# Power_Board.net
KiCad netlist of a schematic drawn in Altium Designer
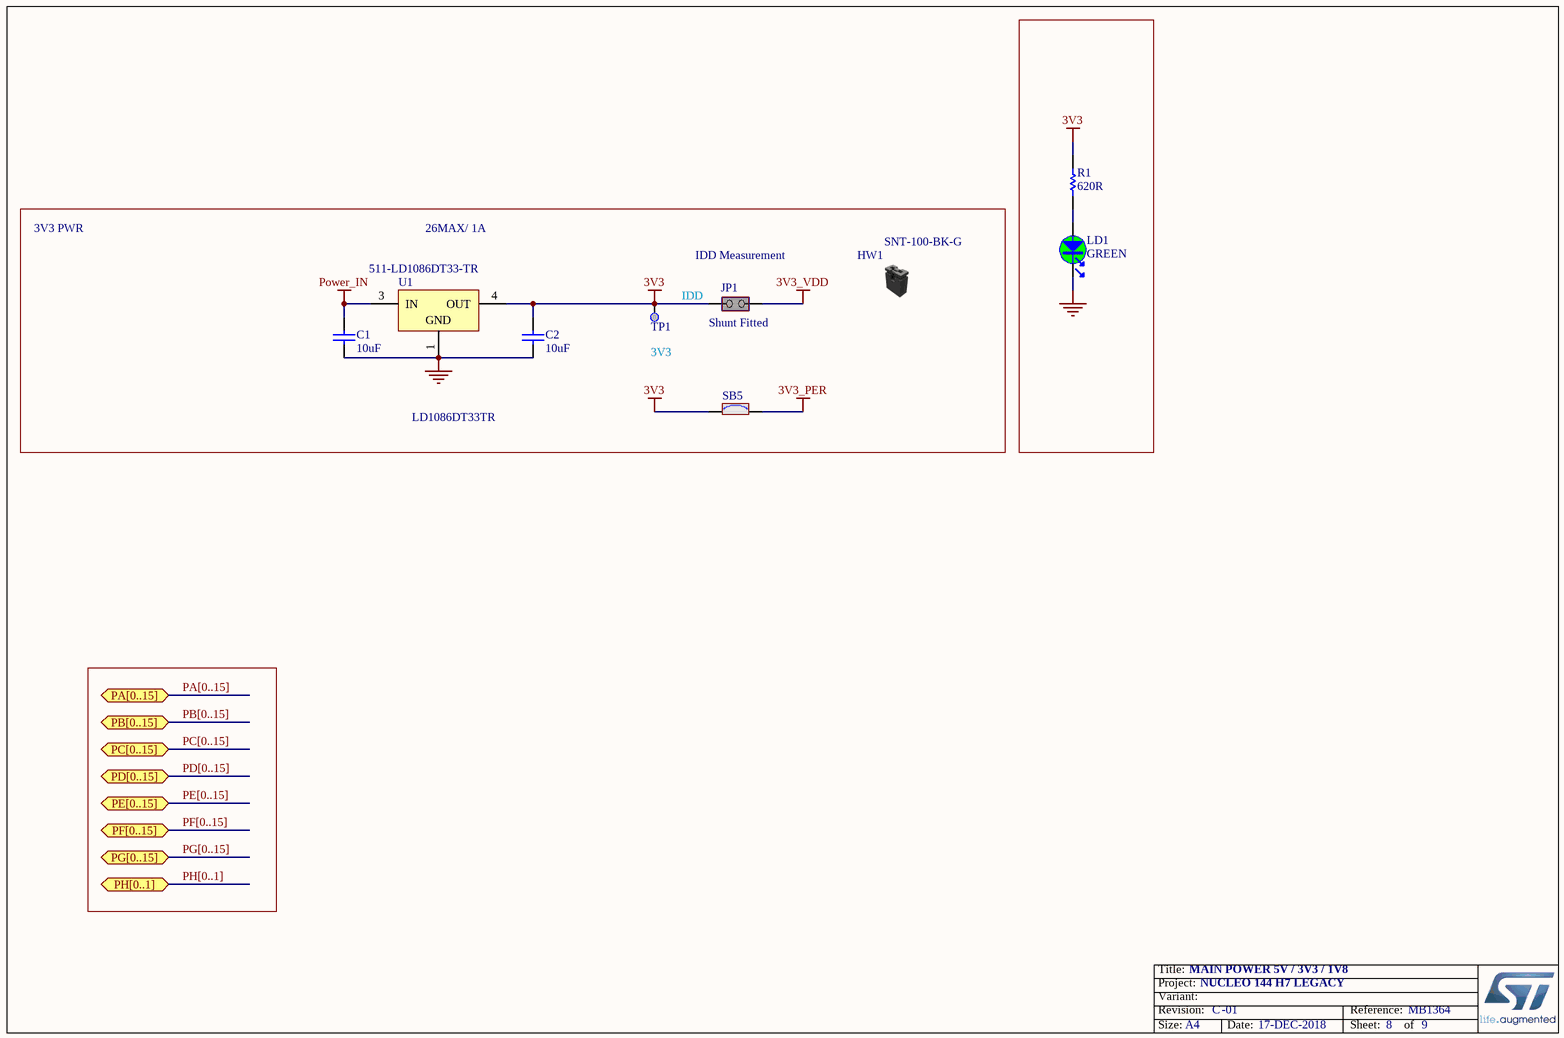
[diagram p0: Power_Board.SchDoc]

(export (version "E")
  (design (tool "Eeschema 10.0.6"))
  (components
    (comp (ref "C1")
      (value "10uF")
      (footprint "C0805")
      (description "Capacitor, MLCC, 10uF, 25V, X5R, 10%, 0805, T=0,85mm")
      (fields
        (field (name "INTERNAL_PART_NUMBER") "MCD-00014")
        (field (name "MANUFACTURER_PART_NUMBER") "CC0805KRX5R8BB106")
        (field (name "PROVIDED_BY") "SUBCO")
      )
      (libsource (lib "MCD_PARTS_database") (part "Capacitor"))
    )
    (comp (ref "C2")
      (value "10uF")
      (footprint "C0805")
      (description "Capacitor, MLCC, 10uF, 25V, X5R, 10%, 0805, T=0,85mm")
      (fields
        (field (name "INTERNAL_PART_NUMBER") "MCD-00014")
        (field (name "MANUFACTURER_PART_NUMBER") "CC0805KRX5R8BB106")
        (field (name "PROVIDED_BY") "SUBCO")
      )
      (libsource (lib "MCD_PARTS_database") (part "Capacitor"))
    )
    (comp (ref "HW1")
      (value "SNT-100-BK-G")
      (description "SHUNT 2.54mm BLACK")
      (fields
        (field (name "INTERNAL_PART_NUMBER") "MCD-00043")
        (field (name "MANUFACTURER") "SAMTEC")
        (field (name "PROVIDED_BY") "SUBCO")
      )
      (libsource (lib "MCD_PARTS_database") (part "Shunt Black 2.54mm"))
    )
    (comp (ref "JP1")
      (value "Shunt Fitted")
      (footprint "CON_SAMTEC_TSW-102-07-G-S")
      (description "Header, 2x1, 2,54mm, VR, TH, Height 5.84mm/2.54mm - Shunt Fitted by default")
      (fields
        (field (name "INTERNAL_PART_NUMBER") "MCD-00683")
        (field (name "MANUFACTURER_PART_NUMBER") "TSW-102-07-x-S")
        (field (name "PROVIDED_BY") "SUBCO")
      )
      (libsource (lib "MCD_PARTS_database") (part "Jumper_Header 2x1 Fitted"))
    )
    (comp (ref "LD1")
      (value "GREEN")
      (footprint "LED_0603_OSRAM_LG-Q396-PS-35_GREEN_1A2K_H0P4")
      (description "LED Green, 0603 SMD, Forward Voltage Typ=2V, Max=2.5V")
      (fields
        (field (name "INTERNAL_PART_NUMBER") "MCD-00588")
        (field (name "MANUFACTURER_PART_NUMBER") "LG Q396-PS-35")
        (field (name "PROVIDED_BY") "SUBCO")
      )
      (libsource (lib "MCD_PARTS_database") (part "LED_green"))
    )
    (comp (ref "R1")
      (value "620R")
      (footprint "R0603")
      (description "Resistor,620R,0603,1%,1/10W")
      (fields
        (field (name "INTERNAL_PART_NUMBER") "MCD-00500")
        (field (name "MANUFACTURER_PART_NUMBER") "RC0603FR-07620RL")
        (field (name "PROVIDED_BY") "SUBCO")
      )
      (libsource (lib "MCD_PARTS_database") (part "Resistor"))
    )
    (comp (ref "SB5")
      (value "SB_ON")
      (footprint "SOLDER-BRIDGE_R0603-0R")
      (description "Solder Bridge ON")
      (fields
        (field (name "INTERNAL_PART_NUMBER") "MCD-00071")
        (field (name "MANUFACTURER_PART_NUMBER") "RC0603JR-070RL")
        (field (name "PROVIDED_BY") "SUBCO")
      )
      (libsource (lib "MCD_PARTS_database") (part "SB_ON"))
    )
    (comp (ref "TP1")
      (value "Test Point")
      (footprint "TP_SMD_1MM")
      (description "Test Point 1mm")
      (fields (field (name "INTERNAL_PART_NUMBER") "MCD-00074") (field (name "MANUFACTURER") "n/a"))
      (libsource (lib "MCD_PARTS_database") (part "Test Point"))
    )
    (comp (ref "U1")
      (value "LD1086DT33TR")
      (footprint "TO-252_L")
      (description "1.5A, Low Drop Positive Voltage Regulator, 3.3V, 3-Pin DPAK, Tape and Reel")
      (fields
        (field (name "SUPPLIER PART NUMBER 1") "511-LD1086DT33-TR")
        (field (name "MANUFACTURER") "STMicroelectronics")
      )
      (libsource (lib "Altium Content Vault") (part "PM-REG-LD1085-SOT3"))
    )
  )
  (nets
    (net (code "123") (name "3V3") (class "Default")
      (node (ref "C2") (pin "2") (pinfunction "2_2") (pintype "passive"))
      (node (ref "JP1") (pin "1") (pinfunction "COMMON_1") (pintype "passive"))
      (node (ref "R1") (pin "2") (pinfunction "2_2") (pintype "passive"))
      (node (ref "SB5") (pin "1") (pinfunction "1_1") (pintype "passive"))
      (node (ref "TP1") (pin "1") (pinfunction "1_1") (pintype "passive"))
      (node (ref "U1") (pin "4") (pinfunction "OUT_4") (pintype "power_in"))
    )
    (net (code "124") (name "3V3_PER") (class "Default")
      (node (ref "SB5") (pin "2") (pinfunction "2_2") (pintype "passive"))
    )
    (net (code "125") (name "3V3_VDD") (class "Default")
      (node (ref "JP1") (pin "2") (pinfunction "NO_2") (pintype "passive"))
    )
    (net (code "126") (name "GND") (class "Default")
      (node (ref "C1") (pin "1") (pinfunction "1_1") (pintype "passive"))
      (node (ref "C2") (pin "1") (pinfunction "1_1") (pintype "passive"))
      (node (ref "LD1") (pin "2") (pintype "passive"))
      (node (ref "U1") (pin "1") (pinfunction "GND_1") (pintype "power_in"))
    )
    (net (code "127") (name "Net-(LD1-Pad1)") (class "Default")
      (node (ref "LD1") (pin "1") (pintype "passive"))
      (node (ref "R1") (pin "1") (pinfunction "1_1") (pintype "passive"))
    )
    (net (code "128") (name "Power_IN") (class "Default")
      (node (ref "C1") (pin "2") (pinfunction "2_2") (pintype "passive"))
      (node (ref "U1") (pin "3") (pinfunction "IN_3") (pintype "power_in"))
    )
  )
)
